# InkTime_v6.net
KiCad netlist of a schematic drawn in EAGLE
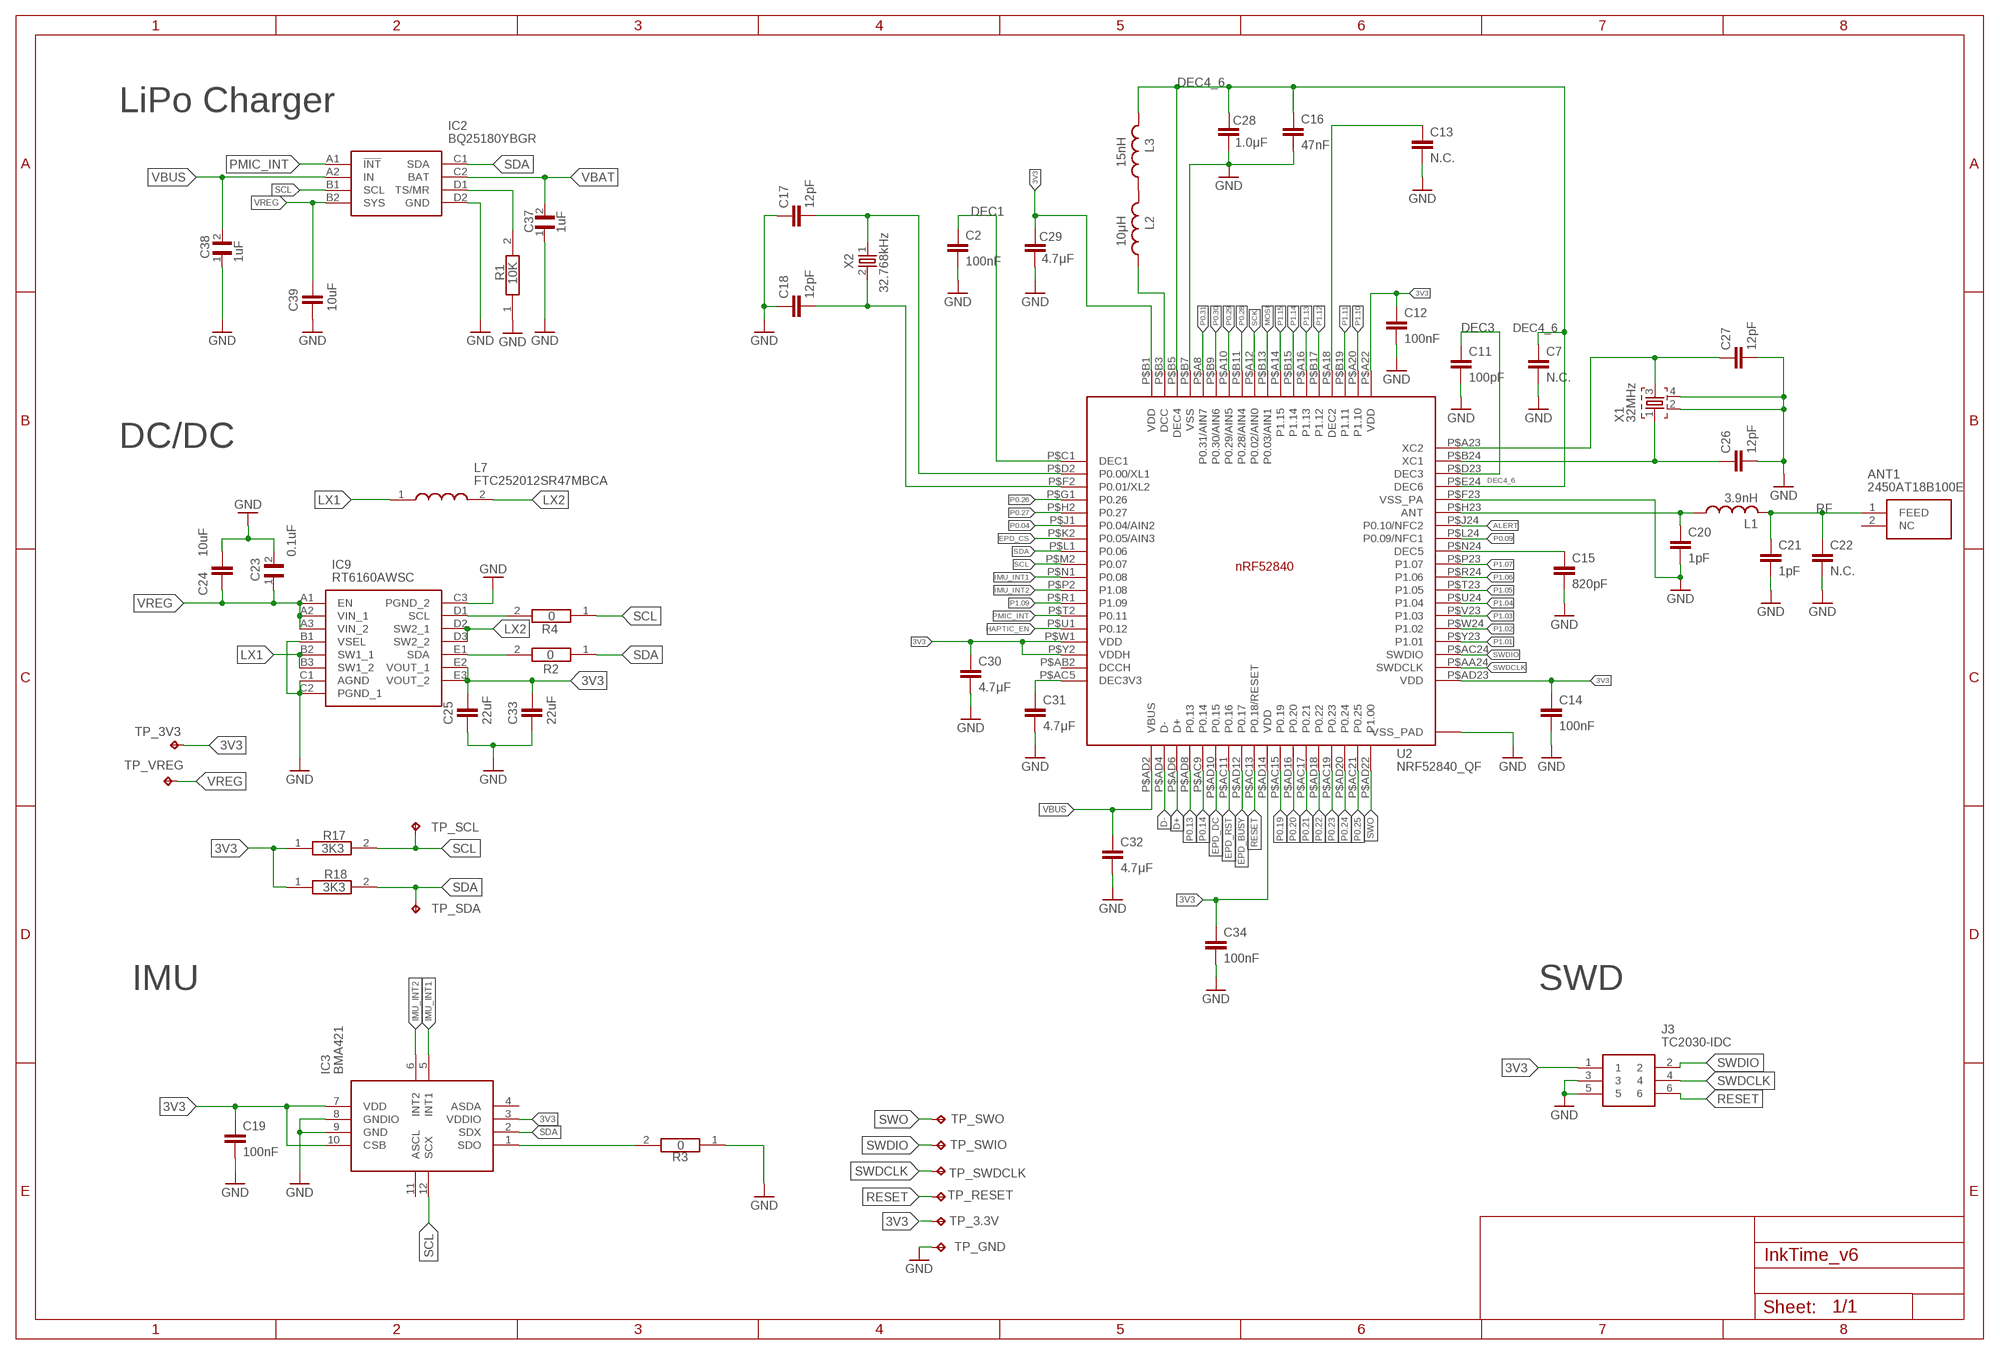
[diagram p0: schematic, sheet 1, part 1 of 2]
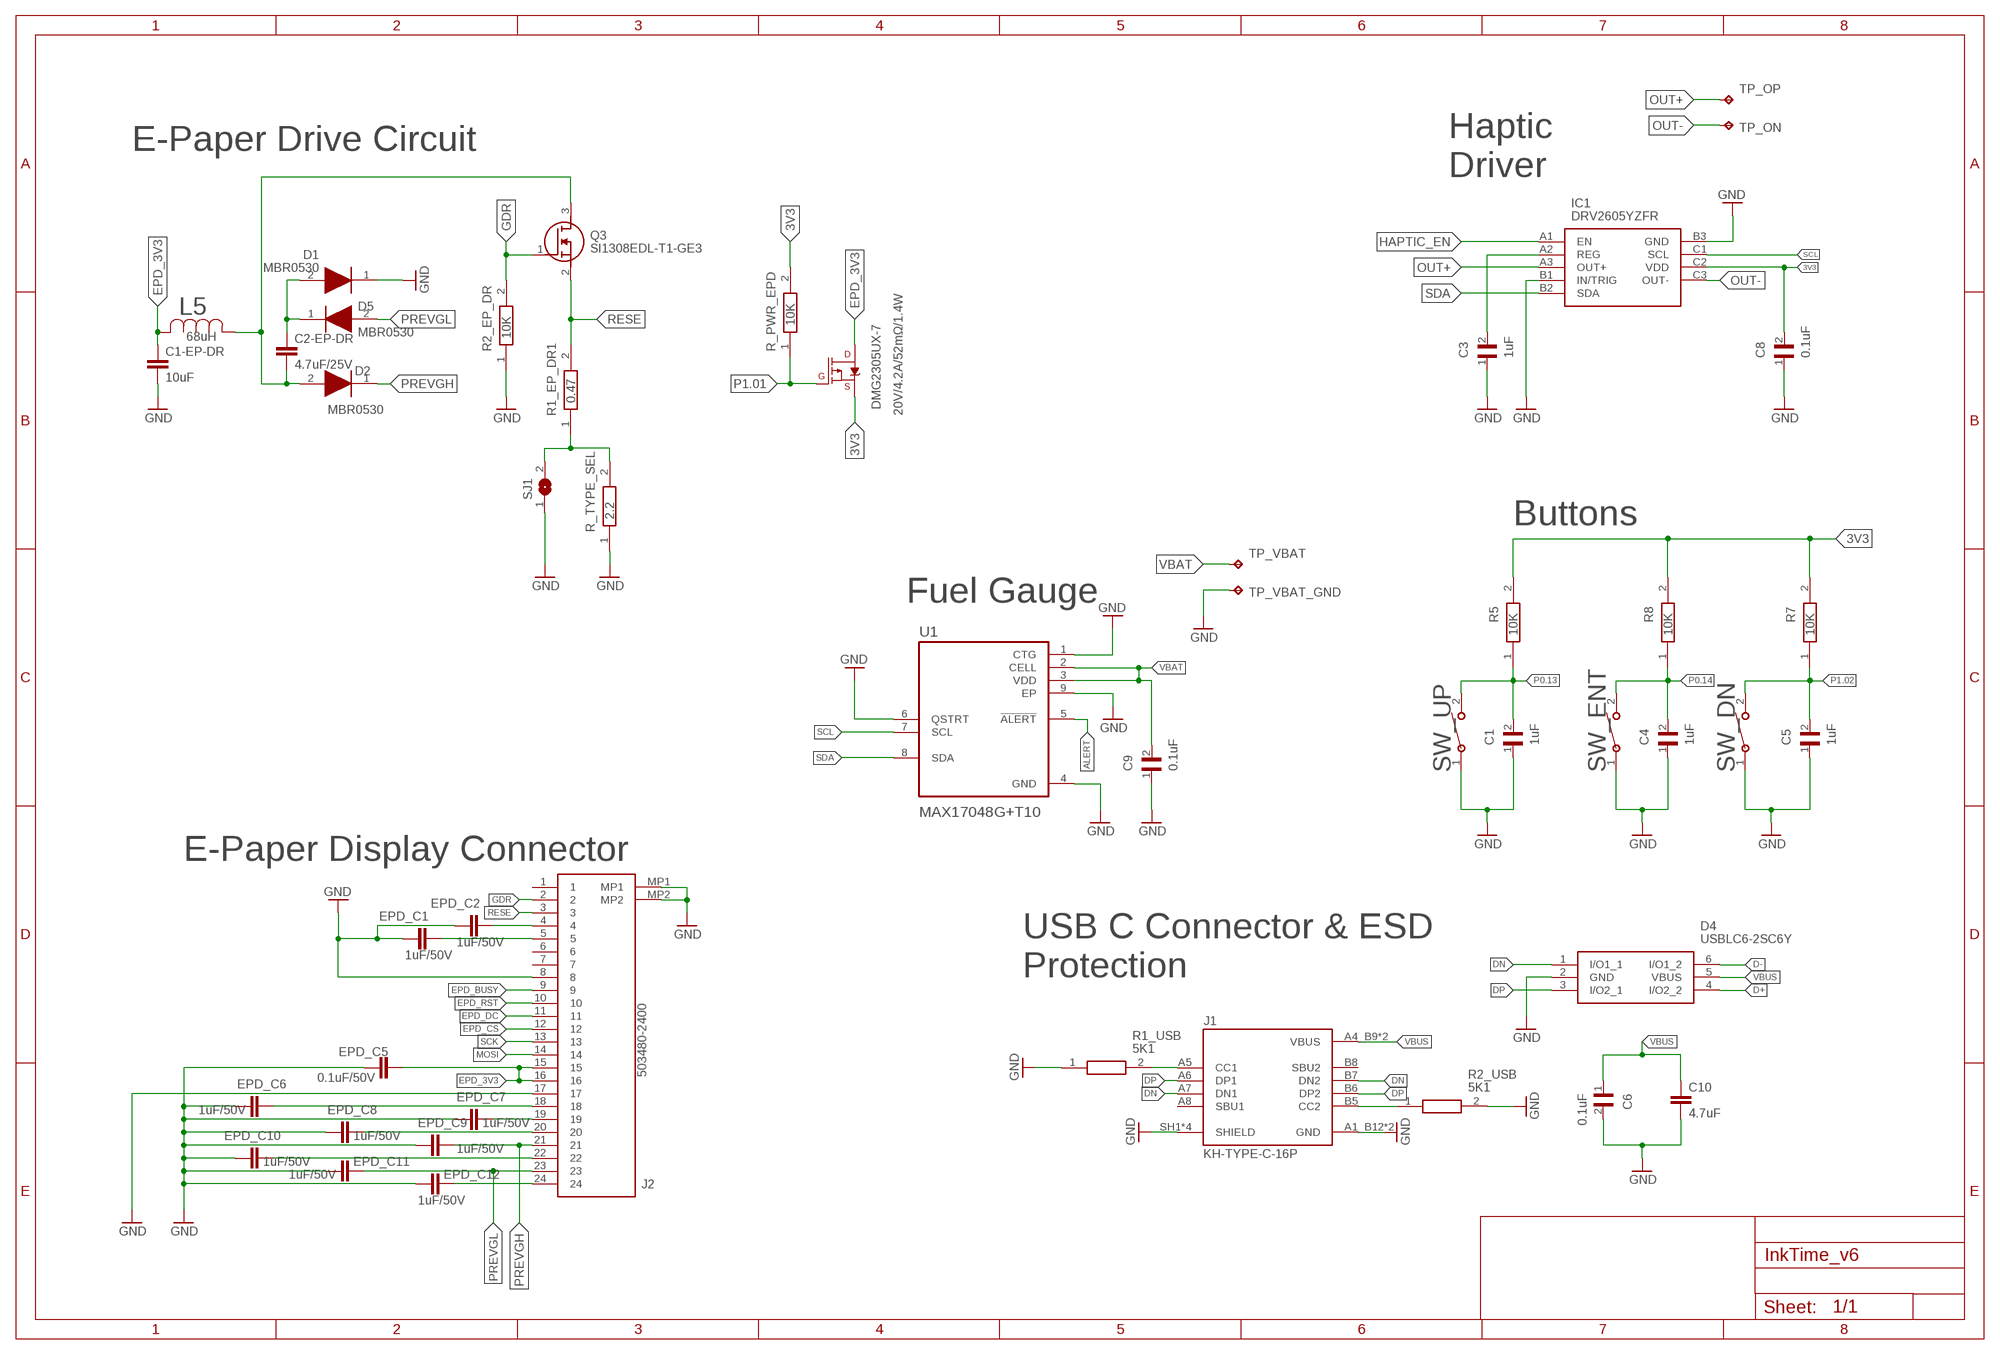
[diagram p1: schematic, sheet 1, part 2 of 2]

(export (version "E")
  (design (tool "Eeschema 10.0.6"))
  (components
    (comp (ref "ANT1")
      (value "2450AT18B100E")
      (footprint "eagle-import:2450AT18B100E_ANTC3216X140N")
      (fields (field (name "MOUSER_PART_NUMBER") "609-2450AT18B100E"))
      (libsource (lib "eagle-import") (part "2450AT18B100E_2450AT18B100E"))
    )
    (comp (ref "C1")
      (value "1uF")
      (footprint "eagle-import:GRM011R60J152KE01L_1_0201")
      (libsource (lib "eagle-import") (part "GRM011R60J152KE01L_1_GRM011R60J152KE01L"))
    )
    (comp (ref "C1-EP-DR")
      (value "10uF")
      (footprint "eagle-import:PERFECT_0402_0402")
      (libsource (lib "eagle-import") (part "PERFECT_0402_CAP_0402"))
    )
    (comp (ref "C2")
      (value "100nF")
      (footprint "eagle-import:NORDIC_NRF_3_RESC0201_L")
      (libsource (lib "eagle-import") (part "NORDIC_NRF_3_CAPACITOR_0201_L"))
    )
    (comp (ref "C2-EP-DR")
      (value "4.7uF/25V")
      (footprint "eagle-import:PERFECT_0402_0402")
      (libsource (lib "eagle-import") (part "PERFECT_0402_CAP_0402"))
    )
    (comp (ref "C3")
      (value "1uF")
      (footprint "eagle-import:GRM011R60J152KE01L_1_0201")
      (libsource (lib "eagle-import") (part "GRM011R60J152KE01L_1_GRM011R60J152KE01L"))
    )
    (comp (ref "C4")
      (value "1uF")
      (footprint "eagle-import:GRM011R60J152KE01L_1_0201")
      (libsource (lib "eagle-import") (part "GRM011R60J152KE01L_1_GRM011R60J152KE01L"))
    )
    (comp (ref "C5")
      (value "1uF")
      (footprint "eagle-import:GRM011R60J152KE01L_1_0201")
      (libsource (lib "eagle-import") (part "GRM011R60J152KE01L_1_GRM011R60J152KE01L"))
    )
    (comp (ref "C6")
      (value "0.1uF")
      (footprint "eagle-import:GRM011R60J152KE01L_1_0201")
      (libsource (lib "eagle-import") (part "GRM011R60J152KE01L_1_GRM011R60J152KE01L"))
    )
    (comp (ref "C7")
      (value "N.C.")
      (footprint "eagle-import:NORDIC_NRF_3_RESC0201_L")
      (libsource (lib "eagle-import") (part "NORDIC_NRF_3_CAPACITOR_0201_L"))
    )
    (comp (ref "C8")
      (value "0.1uF")
      (footprint "eagle-import:GRM011R60J152KE01L_1_0201")
      (libsource (lib "eagle-import") (part "GRM011R60J152KE01L_1_GRM011R60J152KE01L"))
    )
    (comp (ref "C9")
      (value "0.1uF")
      (footprint "eagle-import:GRM011R60J152KE01L_1_0201")
      (libsource (lib "eagle-import") (part "GRM011R60J152KE01L_1_GRM011R60J152KE01L"))
    )
    (comp (ref "C10")
      (value "4.7uF")
      (footprint "eagle-import:PERFECT_0402_0402")
      (libsource (lib "eagle-import") (part "PERFECT_0402_CAP_0402"))
    )
    (comp (ref "C11")
      (value "100pF")
      (footprint "eagle-import:NORDIC_NRF_3_RESC0201_L")
      (libsource (lib "eagle-import") (part "NORDIC_NRF_3_CAPACITOR_0201_L"))
    )
    (comp (ref "C12")
      (value "100nF")
      (footprint "eagle-import:NORDIC_NRF_3_RESC0201_L")
      (libsource (lib "eagle-import") (part "NORDIC_NRF_3_CAPACITOR_0201_L"))
    )
    (comp (ref "C13")
      (value "N.C.")
      (footprint "eagle-import:NORDIC_NRF_3_RESC0201_L")
      (libsource (lib "eagle-import") (part "NORDIC_NRF_3_CAPACITOR_0201_L"))
    )
    (comp (ref "C14")
      (value "100nF")
      (footprint "eagle-import:NORDIC_NRF_3_RESC0201_L")
      (libsource (lib "eagle-import") (part "NORDIC_NRF_3_CAPACITOR_0201_L"))
    )
    (comp (ref "C15")
      (value "820pF")
      (footprint "eagle-import:NORDIC_NRF_3_RESC0201_L")
      (libsource (lib "eagle-import") (part "NORDIC_NRF_3_CAPACITOR_0201_L"))
    )
    (comp (ref "C16")
      (value "47nF")
      (footprint "eagle-import:NORDIC_NRF_3_RESC0201_L")
      (libsource (lib "eagle-import") (part "NORDIC_NRF_3_CAPACITOR_0201_L"))
    )
    (comp (ref "C17")
      (value "12pF")
      (footprint "eagle-import:NORDIC_NRF_3_RESC0201_L")
      (libsource (lib "eagle-import") (part "NORDIC_NRF_3_CAPACITOR_0201_L"))
    )
    (comp (ref "C18")
      (value "12pF")
      (footprint "eagle-import:NORDIC_NRF_3_RESC0201_L")
      (libsource (lib "eagle-import") (part "NORDIC_NRF_3_CAPACITOR_0201_L"))
    )
    (comp (ref "C19")
      (value "100nF")
      (footprint "eagle-import:NORDIC_NRF_3_RESC0201_L")
      (libsource (lib "eagle-import") (part "NORDIC_NRF_3_CAPACITOR_0201_L"))
    )
    (comp (ref "C20")
      (value "1pF")
      (footprint "eagle-import:NORDIC_NRF_3_RESC0201_L")
      (libsource (lib "eagle-import") (part "NORDIC_NRF_3_CAPACITOR_0201_L"))
    )
    (comp (ref "C21")
      (value "1pF")
      (footprint "eagle-import:NORDIC_NRF_3_RESC0201_L")
      (libsource (lib "eagle-import") (part "NORDIC_NRF_3_CAPACITOR_0201_L"))
    )
    (comp (ref "C22")
      (value "N.C.")
      (footprint "eagle-import:NORDIC_NRF_3_RESC0201_L")
      (libsource (lib "eagle-import") (part "NORDIC_NRF_3_CAPACITOR_0201_L"))
    )
    (comp (ref "C23")
      (value "0.1uF")
      (footprint "eagle-import:GRM011R60J152KE01L_2_CAPC0201X13N")
      (fields (field (name "MF") "Murata") (field (name "MP") "GRM011R60J152KE01L"))
      (libsource (lib "eagle-import") (part "GRM011R60J152KE01L_2_GRM011R60J152KE01L"))
    )
    (comp (ref "C24")
      (value "10uF")
      (footprint "eagle-import:NORDIC_NRF_3_RESC0402_L")
      (libsource (lib "eagle-import") (part "NORDIC_NRF_3_CAPACITOR_0402_L"))
    )
    (comp (ref "C25")
      (value "22uF")
      (footprint "eagle-import:NORDIC_NRF_3_RESC0402_L")
      (libsource (lib "eagle-import") (part "NORDIC_NRF_3_CAPACITOR_0402_L"))
    )
    (comp (ref "C26")
      (value "12pF")
      (footprint "eagle-import:NORDIC_NRF_3_RESC0201_L")
      (libsource (lib "eagle-import") (part "NORDIC_NRF_3_CAPACITOR_0201_L"))
    )
    (comp (ref "C27")
      (value "12pF")
      (footprint "eagle-import:NORDIC_NRF_3_RESC0201_L")
      (libsource (lib "eagle-import") (part "NORDIC_NRF_3_CAPACITOR_0201_L"))
    )
    (comp (ref "C28")
      (value "1.0μF")
      (footprint "eagle-import:NORDIC_NRF_3_RESC0402_L")
      (libsource (lib "eagle-import") (part "NORDIC_NRF_3_CAPACITOR_0402_L"))
    )
    (comp (ref "C29")
      (value "4.7μF")
      (footprint "eagle-import:NORDIC_NRF_3_RESC0402_L")
      (libsource (lib "eagle-import") (part "NORDIC_NRF_3_CAPACITOR_0402_L"))
    )
    (comp (ref "C30")
      (value "4.7μF")
      (footprint "eagle-import:NORDIC_NRF_3_RESC0402_L")
      (libsource (lib "eagle-import") (part "NORDIC_NRF_3_CAPACITOR_0402_L"))
    )
    (comp (ref "C31")
      (value "4.7μF")
      (footprint "eagle-import:NORDIC_NRF_3_RESC0402_L")
      (libsource (lib "eagle-import") (part "NORDIC_NRF_3_CAPACITOR_0402_L"))
    )
    (comp (ref "C32")
      (value "4.7μF")
      (footprint "eagle-import:NORDIC_NRF_3_RESC0402_L")
      (libsource (lib "eagle-import") (part "NORDIC_NRF_3_CAPACITOR_0402_L"))
    )
    (comp (ref "C33")
      (value "22uF")
      (footprint "eagle-import:NORDIC_NRF_3_RESC0402_L")
      (libsource (lib "eagle-import") (part "NORDIC_NRF_3_CAPACITOR_0402_L"))
    )
    (comp (ref "C34")
      (value "100nF")
      (footprint "eagle-import:NORDIC_NRF_3_RESC0201_L")
      (libsource (lib "eagle-import") (part "Library_proiect_vf.6mj5mWEzRZml-z0rj9qWig_NORDIC_NRF_3_CAPACITOR_0201_L"))
    )
    (comp (ref "C37")
      (value "1uF")
      (footprint "eagle-import:GRM011R60J152KE01L_2_CAPC0201X13N")
      (fields (field (name "MF") "Murata") (field (name "MP") "GRM011R60J152KE01L"))
      (libsource (lib "eagle-import") (part "GRM011R60J152KE01L_2_GRM011R60J152KE01L"))
    )
    (comp (ref "C38")
      (value "1uF")
      (footprint "eagle-import:GRM011R60J152KE01L_2_CAPC0201X13N")
      (fields (field (name "MF") "Murata") (field (name "MP") "GRM011R60J152KE01L"))
      (libsource (lib "eagle-import") (part "GRM011R60J152KE01L_2_GRM011R60J152KE01L"))
    )
    (comp (ref "C39")
      (value "10uF")
      (footprint "eagle-import:NORDIC_NRF_3_RESC0402_L")
      (libsource (lib "eagle-import") (part "NORDIC_NRF_3_CAPACITOR_0402_L"))
    )
    (comp (ref "D1")
      (value "MBR0530")
      (footprint "eagle-import:ESP32_C6_LIBRARY_5_SOD3716X135N")
      (fields (field (name "MF") "ON Semiconductor"))
      (libsource (lib "eagle-import") (part "ESP32_C6_LIBRARY_5_MBR0530"))
    )
    (comp (ref "D2")
      (value "MBR0530")
      (footprint "eagle-import:ESP32_C6_LIBRARY_5_SOD3716X135N")
      (fields (field (name "MF") "ON Semiconductor"))
      (libsource (lib "eagle-import") (part "ESP32_C6_LIBRARY_5_MBR0530"))
    )
    (comp (ref "D4")
      (value "USBLC6-2SC6Y")
      (footprint "eagle-import:ESP32_C6_LIBRARY_3_SOT95P280X145-6N")
      (fields (field (name "MF") "STMicroelectronics"))
      (libsource (lib "eagle-import") (part "ESP32_C6_LIBRARY_3_USBLC6-2SC6Y"))
    )
    (comp (ref "D5")
      (value "MBR0530")
      (footprint "eagle-import:ESP32_C6_LIBRARY_5_SOD3716X135N")
      (fields (field (name "MF") "ON Semiconductor"))
      (libsource (lib "eagle-import") (part "ESP32_C6_LIBRARY_5_MBR0530"))
    )
    (comp (ref "DMG2305UX-7")
      (value "20V/4.2A/52mΩ/1.4W")
      (footprint "eagle-import:ESP32_C6_LIBRARY_4_ESP32_C6_LIBRARY_4_ESP32_C6_LIBRARY_4_ESP32_C6_LIBRARY_4_ESP32_WROVER_SPARKFUN-DISCRETESEMI_SOT23-3")
      (libsource (lib "eagle-import") (part "ESP32_C6_LIBRARY_4_ESP32_WROVER_SPARKFUN-DISCRETESEMI_MOSFET_PCH-DMG2305UX-7"))
    )
    (comp (ref "EPD_C1")
      (value "1uF/50V")
      (footprint "eagle-import:PERFECT_0402_0402")
      (libsource (lib "eagle-import") (part "PERFECT_0402_CAP_0402"))
    )
    (comp (ref "EPD_C2")
      (value "1uF/50V")
      (footprint "eagle-import:PERFECT_0402_0402")
      (libsource (lib "eagle-import") (part "PERFECT_0402_CAP_0402"))
    )
    (comp (ref "EPD_C5")
      (value "0.1uF/50V")
      (footprint "eagle-import:NORDIC_NRF_3_RESC0201_L")
      (libsource (lib "eagle-import") (part "Library_proiect_vf.6mj5mWEzRZml-z0rj9qWig_NORDIC_NRF_3_CAPACITOR_0201_L"))
    )
    (comp (ref "EPD_C6")
      (value "1uF/50V")
      (footprint "eagle-import:PERFECT_0402_0402")
      (libsource (lib "eagle-import") (part "PERFECT_0402_CAP_0402"))
    )
    (comp (ref "EPD_C7")
      (value "1uF/50V")
      (footprint "eagle-import:PERFECT_0402_0402")
      (libsource (lib "eagle-import") (part "PERFECT_0402_CAP_0402"))
    )
    (comp (ref "EPD_C8")
      (value "1uF/50V")
      (footprint "eagle-import:PERFECT_0402_0402")
      (libsource (lib "eagle-import") (part "PERFECT_0402_CAP_0402"))
    )
    (comp (ref "EPD_C9")
      (value "1uF/50V")
      (footprint "eagle-import:PERFECT_0402_0402")
      (libsource (lib "eagle-import") (part "PERFECT_0402_CAP_0402"))
    )
    (comp (ref "EPD_C10")
      (value "1uF/50V")
      (footprint "eagle-import:PERFECT_0402_0402")
      (libsource (lib "eagle-import") (part "PERFECT_0402_CAP_0402"))
    )
    (comp (ref "EPD_C11")
      (value "1uF/50V")
      (footprint "eagle-import:PERFECT_0402_0402")
      (libsource (lib "eagle-import") (part "PERFECT_0402_CAP_0402"))
    )
    (comp (ref "EPD_C12")
      (value "1uF/50V")
      (footprint "eagle-import:PERFECT_0402_0402")
      (libsource (lib "eagle-import") (part "PERFECT_0402_CAP_0402"))
    )
    (comp (ref "IC1")
      (value "DRV2605YZFR")
      (footprint "eagle-import:DRV2605YZFR_BGA9C50P3X3_144X144X62")
      (libsource (lib "eagle-import") (part "DRV2605YZFR_DRV2605YZFR"))
    )
    (comp (ref "IC2")
      (value "BQ25180YBGR")
      (footprint "eagle-import:BQ25180YBGR_BGA8C40P2X4_100X155X50")
      (fields (field (name "MOUSER_PART_NUMBER") "595-BQ25180YBGR"))
      (libsource (lib "eagle-import") (part "BQ25180YBGR_BQ25180YBGR"))
    )
    (comp (ref "IC3")
      (value "BMA421")
      (footprint "eagle-import:BMA423_BMA423")
      (fields (field (name "ARROW_PART_NUMBER") "BMA423") (field (name "MOUSER_PART_NUMBER") "262-BMA423"))
      (libsource (lib "eagle-import") (part "BMA423_BMA423"))
    )
    (comp (ref "IC9")
      (value "RT6160AWSC")
      (footprint "eagle-import:RT6160AWSC_BGA15C40P3X5_140X230X60")
      (fields (field (name "MOUSER_PART_NUMBER") "835-RT6160AWSC"))
      (libsource (lib "eagle-import") (part "RT6160AWSC_RT6160AWSC"))
    )
    (comp (ref "J1")
      (value "KH-TYPE-C-16P")
      (footprint "eagle-import:KH-TYPE-C-16P_KINGHELM_KH-TYPE-C-16P")
      (fields (field (name "MF") "kinghelm"))
      (libsource (lib "eagle-import") (part "KH-TYPE-C-16P_KH-TYPE-C-16P"))
    )
    (comp (ref "J2")
      (value "503480-2400")
      (footprint "eagle-import:503480-2400_5034802400")
      (fields (field (name "MOUSER_PART_NUMBER") "538-503480-2400"))
      (libsource (lib "eagle-import") (part "503480-2400_503480-2400"))
    )
    (comp (ref "J3")
      (value "TC2030-IDC")
      (footprint "eagle-import:TC2030-IDC_TC2030IDC")
      (libsource (lib "eagle-import") (part "TC2030-IDC_TC2030-IDC"))
    )
    (comp (ref "L1")
      (value "3.9nH")
      (footprint "eagle-import:NORDIC_NRF_2_RESC0402_L")
      (libsource (lib "eagle-import") (part "NORDIC_NRF_2_INDUCTOR_0402_L"))
    )
    (comp (ref "L2")
      (value "10μH")
      (footprint "eagle-import:NORDIC_NRF_2_RESC0402_L")
      (libsource (lib "eagle-import") (part "NORDIC_NRF_2_INDUCTOR_0402_L"))
    )
    (comp (ref "L3")
      (value "15nH")
      (footprint "eagle-import:NORDIC_NRF_2_RESC0402_L")
      (libsource (lib "eagle-import") (part "NORDIC_NRF_2_INDUCTOR_0402_L"))
    )
    (comp (ref "L5")
      (value "68uH")
      (footprint "eagle-import:ESP32_C6_LIBRARY_2_IND_4828-WE-TPC_WRE")
      (fields
        (field (name "MANUFACTURER_PART_NUMBER") "744043680")
        (field (name "COPYRIGHT") "Copyright (C) 2024 Ultra Librarian. All rights reserved.")
      )
      (libsource (lib "eagle-import") (part "ESP32_C6_LIBRARY_2_744043680IND_4828-WE-TPC_WRE"))
    )
    (comp (ref "L7")
      (value "FTC252012SR47MBCA")
      (footprint "eagle-import:MLP2016SR47MT0S1_INDC2016X100N")
      (libsource (lib "eagle-import") (part "MLP2016SR47MT0S1_FTC252012SR47MBCA"))
    )
    (comp (ref "Q3")
      (value "SI1308EDL-T1-GE3")
      (footprint "eagle-import:ESP32_C6_LIBRARY_6_SOT65P210X110-3N")
      (fields (field (name "MF") "Vishay Siliconix"))
      (libsource (lib "eagle-import") (part "ESP32_C6_LIBRARY_6_SI1308EDL-T1-GE3"))
    )
    (comp (ref "R1")
      (value "10K")
      (footprint "eagle-import:CPF0201D7K68C1_0201")
      (libsource (lib "eagle-import") (part "CPF0201D7K68C1_CPF0201D7K68C1"))
    )
    (comp (ref "R1_EP_DR1")
      (value "0.47")
      (footprint "eagle-import:CPF0201D7K68C1_0201")
      (libsource (lib "eagle-import") (part "Library_proiect_vf.6mj5mWEzRZml-z0rj9qWig_CPF0201D7K68C1_CPF0201D7K68C1"))
    )
    (comp (ref "R1_USB")
      (value "5K1")
      (footprint "eagle-import:CPF0201D7K68C1_0201")
      (libsource (lib "eagle-import") (part "Library_proiect_vf.6mj5mWEzRZml-z0rj9qWig_CPF0201D7K68C1_CPF0201D7K68C1"))
    )
    (comp (ref "R2")
      (value "0")
      (footprint "eagle-import:CPF0201D7K68C1_0201")
      (libsource (lib "eagle-import") (part "CPF0201D7K68C1_CPF0201D7K68C1"))
    )
    (comp (ref "R2_EP_DR")
      (value "10K")
      (footprint "eagle-import:CPF0201D7K68C1_0201")
      (libsource (lib "eagle-import") (part "Library_proiect_vf.6mj5mWEzRZml-z0rj9qWig_CPF0201D7K68C1_CPF0201D7K68C1"))
    )
    (comp (ref "R2_USB")
      (value "5K1")
      (footprint "eagle-import:CPF0201D7K68C1_0201")
      (libsource (lib "eagle-import") (part "Library_proiect_vf.6mj5mWEzRZml-z0rj9qWig_CPF0201D7K68C1_CPF0201D7K68C1"))
    )
    (comp (ref "R3")
      (value "0")
      (footprint "eagle-import:CPF0201D7K68C1_0201")
      (libsource (lib "eagle-import") (part "CPF0201D7K68C1_CPF0201D7K68C1"))
    )
    (comp (ref "R4")
      (value "0")
      (footprint "eagle-import:CPF0201D7K68C1_0201")
      (libsource (lib "eagle-import") (part "CPF0201D7K68C1_CPF0201D7K68C1"))
    )
    (comp (ref "R5")
      (value "10K")
      (footprint "eagle-import:CPF0201D7K68C1_0201")
      (libsource (lib "eagle-import") (part "Library_proiect_vf.6mj5mWEzRZml-z0rj9qWig_CPF0201D7K68C1_CPF0201D7K68C1"))
    )
    (comp (ref "R7")
      (value "10K")
      (footprint "eagle-import:CPF0201D7K68C1_0201")
      (libsource (lib "eagle-import") (part "Library_proiect_vf.6mj5mWEzRZml-z0rj9qWig_CPF0201D7K68C1_CPF0201D7K68C1"))
    )
    (comp (ref "R8")
      (value "10K")
      (footprint "eagle-import:CPF0201D7K68C1_0201")
      (libsource (lib "eagle-import") (part "Library_proiect_vf.6mj5mWEzRZml-z0rj9qWig_CPF0201D7K68C1_CPF0201D7K68C1"))
    )
    (comp (ref "R17")
      (value "3K3")
      (footprint "eagle-import:ERA-1AEB3401C_0201")
      (libsource (lib "eagle-import") (part "ERA-1AEB3401C_CPF0201D7K68C1"))
    )
    (comp (ref "R18")
      (value "3K3")
      (footprint "eagle-import:ERA-1AEB3401C_0201")
      (libsource (lib "eagle-import") (part "ERA-1AEB3401C_CPF0201D7K68C1"))
    )
    (comp (ref "R_PWR_EPD")
      (value "10K")
      (footprint "eagle-import:CPF0201D7K68C1_0201")
      (libsource (lib "eagle-import") (part "Library_proiect_vf.6mj5mWEzRZml-z0rj9qWig_CPF0201D7K68C1_CPF0201D7K68C1"))
    )
    (comp (ref "R_TYPE_SEL")
      (value "2.2")
      (footprint "eagle-import:CPF0201D7K68C1_0201")
      (libsource (lib "eagle-import") (part "Library_proiect_vf.6mj5mWEzRZml-z0rj9qWig_CPF0201D7K68C1_CPF0201D7K68C1"))
    )
    (comp (ref "SJ1")
      (value "ESP32_C6_LIBRARY_7_JUMPER_SJ")
      (footprint "eagle-import:ESP32_C6_LIBRARY_7_JUMPER_SJ")
      (libsource (lib "eagle-import") (part "ESP32_C6_LIBRARY_7_JUMPER_SJ"))
    )
    (comp (ref "SW_DN")
      (value "2025-10-22_07-23-44_LIBRARY_EVP-AKE31ASW_EVP-AKE31A_PAN")
      (footprint "eagle-import:2025-10-22_07-23-44_LIBRARY_SW_EVP-AKE31A_PAN")
      (fields
        (field (name "MANUFACTURER_PART_NUMBER") "EVP-AKE31A")
        (field (name "COPYRIGHT") "Copyright (C) 2025 Ultra Librarian. All rights reserved.")
      )
      (libsource (lib "eagle-import") (part "2025-10-22_07-23-44_LIBRARY_EVP-AKE31ASW_EVP-AKE31A_PAN"))
    )
    (comp (ref "SW_ENT")
      (value "2025-10-22_07-23-44_LIBRARY_EVP-AKE31ASW_EVP-AKE31A_PAN")
      (footprint "eagle-import:2025-10-22_07-23-44_LIBRARY_SW_EVP-AKE31A_PAN")
      (fields
        (field (name "MANUFACTURER_PART_NUMBER") "EVP-AKE31A")
        (field (name "COPYRIGHT") "Copyright (C) 2025 Ultra Librarian. All rights reserved.")
      )
      (libsource (lib "eagle-import") (part "2025-10-22_07-23-44_LIBRARY_EVP-AKE31ASW_EVP-AKE31A_PAN"))
    )
    (comp (ref "SW_UP")
      (value "2025-10-22_07-23-44_LIBRARY_EVP-AKE31ASW_EVP-AKE31A_PAN")
      (footprint "eagle-import:2025-10-22_07-23-44_LIBRARY_SW_EVP-AKE31A_PAN")
      (fields
        (field (name "MANUFACTURER_PART_NUMBER") "EVP-AKE31A")
        (field (name "COPYRIGHT") "Copyright (C) 2025 Ultra Librarian. All rights reserved.")
      )
      (libsource (lib "eagle-import") (part "2025-10-22_07-23-44_LIBRARY_EVP-AKE31ASW_EVP-AKE31A_PAN"))
    )
    (comp (ref "TP_3.3V")
      (value "HECTOR_WATCH_1_TPTP20R")
      (footprint "eagle-import:HECTOR_WATCH_1_TP20R")
      (libsource (lib "eagle-import") (part "HECTOR_WATCH_1_TPTP20R"))
    )
    (comp (ref "TP_3V3")
      (value "HECTOR_WATCH_1_TPTP20R")
      (footprint "eagle-import:HECTOR_WATCH_1_TP20R")
      (libsource (lib "eagle-import") (part "HECTOR_WATCH_1_TPTP20R"))
    )
    (comp (ref "TP_GND")
      (value "HECTOR_WATCH_1_TPTP20R")
      (footprint "eagle-import:HECTOR_WATCH_1_TP20R")
      (libsource (lib "eagle-import") (part "HECTOR_WATCH_1_TPTP20R"))
    )
    (comp (ref "TP_ON")
      (value "HECTOR_WATCH_1_TPTP20R")
      (footprint "eagle-import:HECTOR_WATCH_1_TP20R")
      (libsource (lib "eagle-import") (part "Library_proiect_vf.6mj5mWEzRZml-z0rj9qWig_HECTOR_WATCH_1_TPTP20R"))
    )
    (comp (ref "TP_OP")
      (value "HECTOR_WATCH_1_TPTP20R")
      (footprint "eagle-import:HECTOR_WATCH_1_TP20R")
      (libsource (lib "eagle-import") (part "Library_proiect_vf.6mj5mWEzRZml-z0rj9qWig_HECTOR_WATCH_1_TPTP20R"))
    )
    (comp (ref "TP_RESET")
      (value "HECTOR_WATCH_1_TPTP20R")
      (footprint "eagle-import:HECTOR_WATCH_1_TP20R")
      (libsource (lib "eagle-import") (part "HECTOR_WATCH_1_TPTP20R"))
    )
    (comp (ref "TP_SCL")
      (value "HECTOR_WATCH_1_TPTP20R")
      (footprint "eagle-import:HECTOR_WATCH_1_TP20R")
      (libsource (lib "eagle-import") (part "HECTOR_WATCH_1_TPTP20R"))
    )
    (comp (ref "TP_SDA")
      (value "HECTOR_WATCH_1_TPTP20R")
      (footprint "eagle-import:HECTOR_WATCH_1_TP20R")
      (libsource (lib "eagle-import") (part "HECTOR_WATCH_1_TPTP20R"))
    )
    (comp (ref "TP_SWDCLK")
      (value "HECTOR_WATCH_1_TPTP20R")
      (footprint "eagle-import:HECTOR_WATCH_1_TP20R")
      (libsource (lib "eagle-import") (part "HECTOR_WATCH_1_TPTP20R"))
    )
    (comp (ref "TP_SWIO")
      (value "HECTOR_WATCH_1_TPTP20R")
      (footprint "eagle-import:HECTOR_WATCH_1_TP20R")
      (libsource (lib "eagle-import") (part "HECTOR_WATCH_1_TPTP20R"))
    )
    (comp (ref "TP_SWO")
      (value "HECTOR_WATCH_1_TPTP20R")
      (footprint "eagle-import:HECTOR_WATCH_1_TP20R")
      (libsource (lib "eagle-import") (part "HECTOR_WATCH_1_TPTP20R"))
    )
    (comp (ref "TP_VBAT")
      (value "HECTOR_WATCH_1_TPTP20R")
      (footprint "eagle-import:HECTOR_WATCH_1_TP20R")
      (libsource (lib "eagle-import") (part "Library_proiect_vf.6mj5mWEzRZml-z0rj9qWig_HECTOR_WATCH_1_TPTP20R"))
    )
    (comp (ref "TP_VBAT_GND")
      (value "HECTOR_WATCH_1_TPTP20R")
      (footprint "eagle-import:HECTOR_WATCH_1_TP20R")
      (libsource (lib "eagle-import") (part "Library_proiect_vf.6mj5mWEzRZml-z0rj9qWig_HECTOR_WATCH_1_TPTP20R"))
    )
    (comp (ref "TP_VREG")
      (value "HECTOR_WATCH_1_TPTP20R")
      (footprint "eagle-import:HECTOR_WATCH_1_TP20R")
      (libsource (lib "eagle-import") (part "HECTOR_WATCH_1_TPTP20R"))
    )
    (comp (ref "U1")
      (value "MAX17048G+T10")
      (footprint "eagle-import:ESP32_C6_LIBRARY_SON50P200X200X80-9N")
      (fields (field (name "MF") "Analog Devices"))
      (libsource (lib "eagle-import") (part "ESP32_C6_LIBRARY_MAX17048G+T10"))
    )
    (comp (ref "U2")
      (value "NRF52840_QF")
      (footprint "eagle-import:NORDIC_NRF_4_AQFN50P700X700X85_HS-74N")
      (libsource (lib "eagle-import") (part "NORDIC_NRF_4_NRF52840_QF"))
    )
    (comp (ref "X1")
      (value "32MHz")
      (footprint "eagle-import:NORDIC_NRF_BT-XTAL_2016_N")
      (libsource (lib "eagle-import") (part "NORDIC_NRF_XTAL_32MHZ"))
    )
    (comp (ref "X2")
      (value "32.768kHz")
      (footprint "eagle-import:NORDIC_NRF_1_XTAL_3215_N")
      (libsource (lib "eagle-import") (part "NORDIC_NRF_1_XTAL_32KHZ"))
    )
  )
  (nets
    (net (code "1") (name "/DEC1") (class "Default")
      (node (ref "C2") (pin "1") (pinfunction "1_1") (pintype "passive"))
      (node (ref "U2") (pin "P$C1") (pinfunction "DEC1_P$C1") (pintype "power_in"))
    )
    (net (code "2") (name "/DEC3") (class "Default")
      (node (ref "C11") (pin "1") (pinfunction "1_1") (pintype "passive"))
      (node (ref "U2") (pin "P$D23") (pinfunction "DEC3_P$D23") (pintype "bidirectional"))
    )
    (net (code "3") (name "/DEC4_6") (class "Default")
      (node (ref "C16") (pin "1") (pinfunction "1_1") (pintype "passive"))
      (node (ref "C28") (pin "1") (pinfunction "1_1") (pintype "passive"))
      (node (ref "C7") (pin "1") (pinfunction "1_1") (pintype "passive"))
      (node (ref "L3") (pin "2") (pinfunction "2_2") (pintype "passive"))
      (node (ref "U2") (pin "P$B5") (pinfunction "DEC4_P$B5") (pintype "power_in"))
      (node (ref "U2") (pin "P$E24") (pinfunction "DEC6_P$E24") (pintype "bidirectional"))
    )
    (net (code "4") (name "/RF") (class "Default")
      (node (ref "ANT1") (pin "1") (pinfunction "FEED_1") (pintype "input"))
      (node (ref "C21") (pin "1") (pinfunction "1_1") (pintype "passive"))
      (node (ref "C22") (pin "1") (pinfunction "1_1") (pintype "passive"))
      (node (ref "L1") (pin "2") (pinfunction "2_2") (pintype "passive"))
    )
    (net (code "5") (name "3V3") (class "Default")
      (node (ref "C12") (pin "1") (pinfunction "1_1") (pintype "passive"))
      (node (ref "C14") (pin "1") (pinfunction "1_1") (pintype "passive"))
      (node (ref "C19") (pin "1") (pinfunction "1_1") (pintype "passive"))
      (node (ref "C25") (pin "1") (pinfunction "1_1") (pintype "passive"))
      (node (ref "C29") (pin "1") (pinfunction "1_1") (pintype "passive"))
      (node (ref "C30") (pin "1") (pinfunction "1_1") (pintype "passive"))
      (node (ref "C33") (pin "1") (pinfunction "1_1") (pintype "passive"))
      (node (ref "C34") (pin "1") (pinfunction "1_1") (pintype "passive"))
      (node (ref "C8") (pin "2") (pinfunction "2_2") (pintype "passive"))
      (node (ref "DMG2305UX-7") (pin "2") (pinfunction "S_2") (pintype "bidirectional"))
      (node (ref "IC1") (pin "C2") (pinfunction "VDD_C2") (pintype "bidirectional"))
      (node (ref "IC3") (pin "10") (pinfunction "CSB_10") (pintype "bidirectional"))
      (node (ref "IC3") (pin "3") (pinfunction "VDDIO_3") (pintype "bidirectional"))
      (node (ref "IC3") (pin "7") (pinfunction "VDD_7") (pintype "bidirectional"))
      (node (ref "IC9") (pin "E2") (pinfunction "VOUT_1_E2") (pintype "bidirectional"))
      (node (ref "IC9") (pin "E3") (pinfunction "VOUT_2_E3") (pintype "bidirectional"))
      (node (ref "J3") (pin "1") (pinfunction "1_1") (pintype "bidirectional"))
      (node (ref "R17") (pin "1") (pinfunction "1_1") (pintype "bidirectional"))
      (node (ref "R18") (pin "1") (pinfunction "1_1") (pintype "bidirectional"))
      (node (ref "R5") (pin "2") (pinfunction "2_2") (pintype "bidirectional"))
      (node (ref "R7") (pin "2") (pinfunction "2_2") (pintype "bidirectional"))
      (node (ref "R8") (pin "2") (pinfunction "2_2") (pintype "bidirectional"))
      (node (ref "R_PWR_EPD") (pin "2") (pinfunction "2_2") (pintype "bidirectional"))
      (node (ref "TP_3.3V") (pin "TP") (pinfunction "TP_TP") (pintype "input"))
      (node (ref "TP_3V3") (pin "TP") (pinfunction "TP_TP") (pintype "input"))
      (node (ref "U2") (pin "P$A22") (pinfunction "VDD_P$A22") (pintype "power_in"))
      (node (ref "U2") (pin "P$AD14") (pinfunction "VDD_P$AD14") (pintype "power_in"))
      (node (ref "U2") (pin "P$AD23") (pinfunction "VDD_P$AD23") (pintype "power_in"))
      (node (ref "U2") (pin "P$B1") (pinfunction "VDD_P$B1") (pintype "power_in"))
      (node (ref "U2") (pin "P$W1") (pinfunction "VDD_P$W1") (pintype "power_in"))
      (node (ref "U2") (pin "P$Y2") (pinfunction "VDDH_P$Y2") (pintype "power_in"))
    )
    (net (code "6") (name "ALERT") (class "Default")
      (node (ref "U1") (pin "5") (pinfunction "~{ALERT}_5") (pintype "output"))
      (node (ref "U2") (pin "P$J24") (pinfunction "P0.10/NFC2_P$J24") (pintype "bidirectional"))
    )
    (net (code "7") (name "D+") (class "Default")
      (node (ref "D4") (pin "4") (pinfunction "I/O2_2_4") (pintype "bidirectional"))
      (node (ref "U2") (pin "P$AD6") (pinfunction "D+_P$AD6") (pintype "bidirectional"))
    )
    (net (code "8") (name "D-") (class "Default")
      (node (ref "D4") (pin "6") (pinfunction "I/O1_2_6") (pintype "bidirectional"))
      (node (ref "U2") (pin "P$AD4") (pinfunction "D-_P$AD4") (pintype "bidirectional"))
    )
    (net (code "9") (name "DN") (class "Default")
      (node (ref "D4") (pin "1") (pinfunction "I/O1_1_1") (pintype "bidirectional"))
      (node (ref "J1") (pin "A7") (pinfunction "DN1_A7") (pintype "bidirectional"))
      (node (ref "J1") (pin "B7") (pinfunction "DN2_B7") (pintype "bidirectional"))
    )
    (net (code "10") (name "DP") (class "Default")
      (node (ref "D4") (pin "3") (pinfunction "I/O2_1_3") (pintype "bidirectional"))
      (node (ref "J1") (pin "A6") (pinfunction "DP1_A6") (pintype "bidirectional"))
      (node (ref "J1") (pin "B6") (pinfunction "DP2_B6") (pintype "bidirectional"))
    )
    (net (code "11") (name "EPD_3V3") (class "Default")
      (node (ref "C1-EP-DR") (pin "1") (pinfunction "1_1") (pintype "passive"))
      (node (ref "DMG2305UX-7") (pin "3") (pinfunction "D_3") (pintype "bidirectional"))
      (node (ref "EPD_C5") (pin "2") (pinfunction "2_2") (pintype "passive"))
      (node (ref "J2") (pin "15") (pinfunction "15_15") (pintype "bidirectional"))
      (node (ref "J2") (pin "16") (pinfunction "16_16") (pintype "bidirectional"))
      (node (ref "L5") (pin "2") (pinfunction "2_2") (pintype "passive"))
    )
    (net (code "12") (name "EPD_BUSY") (class "Default")
      (node (ref "J2") (pin "9") (pinfunction "9_9") (pintype "bidirectional"))
      (node (ref "U2") (pin "P$AD12") (pinfunction "P0.17_P$AD12") (pintype "bidirectional"))
    )
    (net (code "13") (name "EPD_CS") (class "Default")
      (node (ref "J2") (pin "12") (pinfunction "12_12") (pintype "bidirectional"))
      (node (ref "U2") (pin "P$K2") (pinfunction "P0.05/AIN3_P$K2") (pintype "bidirectional"))
    )
    (net (code "14") (name "EPD_DC") (class "Default")
      (node (ref "J2") (pin "11") (pinfunction "11_11") (pintype "bidirectional"))
      (node (ref "U2") (pin "P$AD10") (pinfunction "P0.15_P$AD10") (pintype "bidirectional"))
    )
    (net (code "15") (name "EPD_RST") (class "Default")
      (node (ref "J2") (pin "10") (pinfunction "10_10") (pintype "bidirectional"))
      (node (ref "U2") (pin "P$AC11") (pinfunction "P0.16_P$AC11") (pintype "bidirectional"))
    )
    (net (code "16") (name "GDR") (class "Default")
      (node (ref "J2") (pin "2") (pinfunction "2_2") (pintype "bidirectional"))
      (node (ref "Q3") (pin "1") (pinfunction "G_1") (pintype "bidirectional"))
      (node (ref "R2_EP_DR") (pin "2") (pinfunction "2_2") (pintype "bidirectional"))
    )
    (net (code "17") (name "GND") (class "Default")
      (node (ref "C1") (pin "1") (pinfunction "1_1") (pintype "passive"))
      (node (ref "C1-EP-DR") (pin "2") (pinfunction "2_2") (pintype "passive"))
      (node (ref "C10") (pin "2") (pinfunction "2_2") (pintype "passive"))
      (node (ref "C11") (pin "2") (pinfunction "2_2") (pintype "passive"))
      (node (ref "C12") (pin "2") (pinfunction "2_2") (pintype "passive"))
      (node (ref "C13") (pin "2") (pinfunction "2_2") (pintype "passive"))
      (node (ref "C14") (pin "2") (pinfunction "2_2") (pintype "passive"))
      (node (ref "C15") (pin "2") (pinfunction "2_2") (pintype "passive"))
      (node (ref "C16") (pin "2") (pinfunction "2_2") (pintype "passive"))
      (node (ref "C17") (pin "1") (pinfunction "1_1") (pintype "passive"))
      (node (ref "C18") (pin "1") (pinfunction "1_1") (pintype "passive"))
      (node (ref "C19") (pin "2") (pinfunction "2_2") (pintype "passive"))
      (node (ref "C2") (pin "2") (pinfunction "2_2") (pintype "passive"))
      (node (ref "C20") (pin "2") (pinfunction "2_2") (pintype "passive"))
      (node (ref "C21") (pin "2") (pinfunction "2_2") (pintype "passive"))
      (node (ref "C22") (pin "2") (pinfunction "2_2") (pintype "passive"))
      (node (ref "C23") (pin "2") (pinfunction "2_2") (pintype "passive"))
      (node (ref "C24") (pin "1") (pinfunction "1_1") (pintype "passive"))
      (node (ref "C25") (pin "2") (pinfunction "2_2") (pintype "passive"))
      (node (ref "C26") (pin "2") (pinfunction "2_2") (pintype "passive"))
      (node (ref "C27") (pin "2") (pinfunction "2_2") (pintype "passive"))
      (node (ref "C28") (pin "2") (pinfunction "2_2") (pintype "passive"))
      (node (ref "C29") (pin "2") (pinfunction "2_2") (pintype "passive"))
      (node (ref "C3") (pin "1") (pinfunction "1_1") (pintype "passive"))
      (node (ref "C30") (pin "2") (pinfunction "2_2") (pintype "passive"))
      (node (ref "C31") (pin "2") (pinfunction "2_2") (pintype "passive"))
      (node (ref "C32") (pin "2") (pinfunction "2_2") (pintype "passive"))
      (node (ref "C33") (pin "2") (pinfunction "2_2") (pintype "passive"))
      (node (ref "C34") (pin "2") (pinfunction "2_2") (pintype "passive"))
      (node (ref "C37") (pin "1") (pinfunction "1_1") (pintype "passive"))
      (node (ref "C38") (pin "1") (pinfunction "1_1") (pintype "passive"))
      (node (ref "C39") (pin "2") (pinfunction "2_2") (pintype "passive"))
      (node (ref "C4") (pin "1") (pinfunction "1_1") (pintype "passive"))
      (node (ref "C5") (pin "1") (pinfunction "1_1") (pintype "passive"))
      (node (ref "C6") (pin "2") (pinfunction "2_2") (pintype "passive"))
      (node (ref "C7") (pin "2") (pinfunction "2_2") (pintype "passive"))
      (node (ref "C8") (pin "1") (pinfunction "1_1") (pintype "passive"))
      (node (ref "C9") (pin "1") (pinfunction "1_1") (pintype "passive"))
      (node (ref "D1") (pin "1") (pinfunction "K_1") (pintype "bidirectional"))
      (node (ref "D4") (pin "2") (pinfunction "GND_2") (pintype "bidirectional"))
      (node (ref "EPD_C1") (pin "2") (pinfunction "2_2") (pintype "passive"))
      (node (ref "EPD_C10") (pin "2") (pinfunction "2_2") (pintype "passive"))
      (node (ref "EPD_C11") (pin "2") (pinfunction "2_2") (pintype "passive"))
      (node (ref "EPD_C12") (pin "2") (pinfunction "2_2") (pintype "passive"))
      (node (ref "EPD_C2") (pin "2") (pinfunction "2_2") (pintype "passive"))
      (node (ref "EPD_C5") (pin "1") (pinfunction "1_1") (pintype "passive"))
      (node (ref "EPD_C6") (pin "2") (pinfunction "2_2") (pintype "passive"))
      (node (ref "EPD_C7") (pin "2") (pinfunction "2_2") (pintype "passive"))
      (node (ref "EPD_C8") (pin "2") (pinfunction "2_2") (pintype "passive"))
      (node (ref "EPD_C9") (pin "2") (pinfunction "2_2") (pintype "passive"))
      (node (ref "IC1") (pin "B1") (pinfunction "IN/TRIG_B1") (pintype "bidirectional"))
      (node (ref "IC1") (pin "B3") (pinfunction "GND_B3") (pintype "bidirectional"))
      (node (ref "IC2") (pin "D2") (pinfunction "GND_D2") (pintype "bidirectional"))
      (node (ref "IC3") (pin "8") (pinfunction "GNDIO_8") (pintype "bidirectional"))
      (node (ref "IC3") (pin "9") (pinfunction "GND_9") (pintype "bidirectional"))
      (node (ref "IC9") (pin "B1") (pinfunction "VSEL_B1") (pintype "bidirectional"))
      (node (ref "IC9") (pin "C1") (pinfunction "AGND_C1") (pintype "bidirectional"))
      (node (ref "IC9") (pin "C2") (pinfunction "PGND_1_C2") (pintype "bidirectional"))
      (node (ref "IC9") (pin "C3") (pinfunction "PGND_2_C3") (pintype "bidirectional"))
      (node (ref "J1") (pin "A12_B1") (pinfunction "GND_A12_B1") (pintype "power_in"))
      (node (ref "J1") (pin "A1_B12") (pinfunction "GND_A1_B12") (pintype "power_in"))
      (node (ref "J1") (pin "SH1") (pinfunction "SHIELD_SH1") (pintype "passive"))
      (node (ref "J1") (pin "SH2") (pinfunction "SHIELD_SH2") (pintype "passive"))
      (node (ref "J1") (pin "SH3") (pinfunction "SHIELD_SH3") (pintype "passive"))
      (node (ref "J1") (pin "SH4") (pinfunction "SHIELD_SH4") (pintype "passive"))
      (node (ref "J2") (pin "17") (pinfunction "17_17") (pintype "bidirectional"))
      (node (ref "J2") (pin "8") (pinfunction "8_8") (pintype "bidirectional"))
      (node (ref "J2") (pin "MP1") (pinfunction "MP1_MP1") (pintype "bidirectional"))
      (node (ref "J2") (pin "MP2") (pinfunction "MP2_MP2") (pintype "bidirectional"))
      (node (ref "J3") (pin "3") (pinfunction "3_3") (pintype "bidirectional"))
      (node (ref "J3") (pin "5") (pinfunction "5_5") (pintype "bidirectional"))
      (node (ref "R1") (pin "1") (pinfunction "1_1") (pintype "bidirectional"))
      (node (ref "R1_USB") (pin "1") (pinfunction "1_1") (pintype "bidirectional"))
      (node (ref "R2_EP_DR") (pin "1") (pinfunction "1_1") (pintype "bidirectional"))
      (node (ref "R2_USB") (pin "2") (pinfunction "2_2") (pintype "bidirectional"))
      (node (ref "R3") (pin "1") (pinfunction "1_1") (pintype "bidirectional"))
      (node (ref "R_TYPE_SEL") (pin "1") (pinfunction "1_1") (pintype "bidirectional"))
      (node (ref "SJ1") (pin "1") (pinfunction "1_1") (pintype "passive"))
      (node (ref "SW_DN") (pin "1") (pinfunction "1_1") (pintype "passive"))
      (node (ref "SW_ENT") (pin "1") (pinfunction "1_1") (pintype "passive"))
      (node (ref "SW_UP") (pin "1") (pinfunction "1_1") (pintype "passive"))
      (node (ref "TP_GND") (pin "TP") (pinfunction "TP_TP") (pintype "input"))
      (node (ref "TP_VBAT_GND") (pin "TP") (pinfunction "TP_TP") (pintype "input"))
      (node (ref "U1") (pin "1") (pinfunction "CTG_1") (pintype "power_in"))
      (node (ref "U1") (pin "4") (pinfunction "GND_4") (pintype "power_in"))
      (node (ref "U1") (pin "6") (pinfunction "QSTRT_6") (pintype "input"))
      (node (ref "U1") (pin "9") (pinfunction "EP_9") (pintype "power_in"))
      (node (ref "U2") (pin "P$74") (pinfunction "VSS_PAD_P$74") (pintype "bidirectional"))
      (node (ref "U2") (pin "P$75") (pinfunction "VSS_PAD_P$75") (pintype "bidirectional"))
      (node (ref "U2") (pin "P$76") (pinfunction "VSS_PAD_P$76") (pintype "bidirectional"))
      (node (ref "U2") (pin "P$77") (pinfunction "VSS_PAD_P$77") (pintype "bidirectional"))
      (node (ref "U2") (pin "P$78") (pinfunction "VSS_PAD_P$78") (pintype "bidirectional"))
      (node (ref "U2") (pin "P$79") (pinfunction "VSS_PAD_P$79") (pintype "bidirectional"))
      (node (ref "U2") (pin "P$80") (pinfunction "VSS_PAD_P$80") (pintype "bidirectional"))
      (node (ref "U2") (pin "P$81") (pinfunction "VSS_PAD_P$81") (pintype "bidirectional"))
      (node (ref "U2") (pin "P$82") (pinfunction "VSS_PAD_P$82") (pintype "bidirectional"))
      (node (ref "U2") (pin "P$83") (pinfunction "VSS_PAD_P$83") (pintype "bidirectional"))
      (node (ref "U2") (pin "P$84") (pinfunction "VSS_PAD_P$84") (pintype "bidirectional"))
      (node (ref "U2") (pin "P$85") (pinfunction "VSS_PAD_P$85") (pintype "bidirectional"))
      (node (ref "U2") (pin "P$86") (pinfunction "VSS_PAD_P$86") (pintype "bidirectional"))
      (node (ref "U2") (pin "P$87") (pinfunction "VSS_PAD_P$87") (pintype "bidirectional"))
      (node (ref "U2") (pin "P$88") (pinfunction "VSS_PAD_P$88") (pintype "bidirectional"))
      (node (ref "U2") (pin "P$89") (pinfunction "VSS_PAD_P$89") (pintype "bidirectional"))
      (node (ref "U2") (pin "P$90") (pinfunction "VSS_PAD_P$90") (pintype "bidirectional"))
      (node (ref "U2") (pin "P$B7") (pinfunction "VSS_P$B7") (pintype "power_in"))
      (node (ref "U2") (pin "P$F23") (pinfunction "VSS_PA_P$F23") (pintype "bidirectional"))
      (node (ref "X1") (pin "2") (pinfunction "2_2") (pintype "passive"))
      (node (ref "X1") (pin "4") (pinfunction "4_4") (pintype "passive"))
    )
    (net (code "18") (name "HAPTIC_EN") (class "Default")
      (node (ref "IC1") (pin "A1") (pinfunction "EN_A1") (pintype "bidirectional"))
      (node (ref "U2") (pin "P$U1") (pinfunction "P0.12_P$U1") (pintype "bidirectional"))
    )
    (net (code "19") (name "IMU_INT1") (class "Default")
      (node (ref "IC3") (pin "5") (pinfunction "INT1_5") (pintype "bidirectional"))
      (node (ref "U2") (pin "P$N1") (pinfunction "P0.08_P$N1") (pintype "bidirectional"))
    )
    (net (code "20") (name "IMU_INT2") (class "Default")
      (node (ref "IC3") (pin "6") (pinfunction "INT2_6") (pintype "bidirectional"))
      (node (ref "U2") (pin "P$P2") (pinfunction "P1.08_P$P2") (pintype "bidirectional"))
    )
    (net (code "21") (name "LX1") (class "Default")
      (node (ref "IC9") (pin "B2") (pinfunction "SW1_1_B2") (pintype "bidirectional"))
      (node (ref "IC9") (pin "B3") (pinfunction "SW1_2_B3") (pintype "bidirectional"))
      (node (ref "L7") (pin "1") (pinfunction "1_1") (pintype "bidirectional"))
    )
    (net (code "22") (name "LX2") (class "Default")
      (node (ref "IC9") (pin "D2") (pinfunction "SW2_1_D2") (pintype "bidirectional"))
      (node (ref "IC9") (pin "D3") (pinfunction "SW2_2_D3") (pintype "bidirectional"))
      (node (ref "L7") (pin "2") (pinfunction "2_2") (pintype "bidirectional"))
    )
    (net (code "23") (name "MOSI") (class "Default")
      (node (ref "J2") (pin "14") (pinfunction "14_14") (pintype "bidirectional"))
      (node (ref "U2") (pin "P$B13") (pinfunction "P0.03/AIN1_P$B13") (pintype "bidirectional"))
    )
    (net (code "24") (name "Net-(D1-A)") (class "Default")
      (node (ref "C2-EP-DR") (pin "1") (pinfunction "1_1") (pintype "passive"))
      (node (ref "D1") (pin "2") (pinfunction "A_2") (pintype "bidirectional"))
      (node (ref "D5") (pin "1") (pinfunction "K_1") (pintype "bidirectional"))
    )
    (net (code "25") (name "Net-(D2-A)") (class "Default")
      (node (ref "C2-EP-DR") (pin "2") (pinfunction "2_2") (pintype "passive"))
      (node (ref "D2") (pin "2") (pinfunction "A_2") (pintype "bidirectional"))
      (node (ref "L5") (pin "1") (pinfunction "1_1") (pintype "passive"))
      (node (ref "Q3") (pin "3") (pinfunction "D_3") (pintype "bidirectional"))
    )
    (net (code "26") (name "Net-(EPD_C1-Pad1)") (class "Default")
      (node (ref "EPD_C1") (pin "1") (pinfunction "1_1") (pintype "passive"))
      (node (ref "J2") (pin "5") (pinfunction "5_5") (pintype "bidirectional"))
    )
    (net (code "27") (name "Net-(EPD_C2-Pad1)") (class "Default")
      (node (ref "EPD_C2") (pin "1") (pinfunction "1_1") (pintype "passive"))
      (node (ref "J2") (pin "4") (pinfunction "4_4") (pintype "bidirectional"))
    )
    (net (code "28") (name "Net-(EPD_C6-Pad1)") (class "Default")
      (node (ref "EPD_C6") (pin "1") (pinfunction "1_1") (pintype "passive"))
      (node (ref "J2") (pin "18") (pinfunction "18_18") (pintype "bidirectional"))
    )
    (net (code "29") (name "Net-(EPD_C7-Pad1)") (class "Default")
      (node (ref "EPD_C7") (pin "1") (pinfunction "1_1") (pintype "passive"))
      (node (ref "J2") (pin "19") (pinfunction "19_19") (pintype "bidirectional"))
    )
    (net (code "30") (name "Net-(EPD_C8-Pad1)") (class "Default")
      (node (ref "EPD_C8") (pin "1") (pinfunction "1_1") (pintype "passive"))
      (node (ref "J2") (pin "20") (pinfunction "20_20") (pintype "bidirectional"))
    )
    (net (code "31") (name "Net-(EPD_C10-Pad1)") (class "Default")
      (node (ref "EPD_C10") (pin "1") (pinfunction "1_1") (pintype "passive"))
      (node (ref "J2") (pin "22") (pinfunction "22_22") (pintype "bidirectional"))
    )
    (net (code "32") (name "Net-(EPD_C12-Pad1)") (class "Default")
      (node (ref "EPD_C12") (pin "1") (pinfunction "1_1") (pintype "passive"))
      (node (ref "J2") (pin "24") (pinfunction "24_24") (pintype "bidirectional"))
    )
    (net (code "33") (name "Net-(IC1-REG)") (class "Default")
      (node (ref "C3") (pin "2") (pinfunction "2_2") (pintype "passive"))
      (node (ref "IC1") (pin "A2") (pinfunction "REG_A2") (pintype "bidirectional"))
    )
    (net (code "34") (name "Net-(IC2-TS{slash}MR)") (class "Default")
      (node (ref "IC2") (pin "D1") (pinfunction "TS/MR_D1") (pintype "bidirectional"))
      (node (ref "R1") (pin "2") (pinfunction "2_2") (pintype "bidirectional"))
    )
    (net (code "35") (name "Net-(IC3-SDO)") (class "Default")
      (node (ref "IC3") (pin "1") (pinfunction "SDO_1") (pintype "bidirectional"))
      (node (ref "R3") (pin "2") (pinfunction "2_2") (pintype "bidirectional"))
    )
    (net (code "36") (name "Net-(IC9-SCL)") (class "Default")
      (node (ref "IC9") (pin "D1") (pinfunction "SCL_D1") (pintype "bidirectional"))
      (node (ref "R4") (pin "2") (pinfunction "2_2") (pintype "bidirectional"))
    )
    (net (code "37") (name "Net-(IC9-SDA)") (class "Default")
      (node (ref "IC9") (pin "E1") (pinfunction "SDA_E1") (pintype "bidirectional"))
      (node (ref "R2") (pin "2") (pinfunction "2_2") (pintype "bidirectional"))
    )
    (net (code "38") (name "Net-(J1-CC1)") (class "Default")
      (node (ref "J1") (pin "A5") (pinfunction "CC1_A5") (pintype "bidirectional"))
      (node (ref "R1_USB") (pin "2") (pinfunction "2_2") (pintype "bidirectional"))
    )
    (net (code "39") (name "Net-(J1-CC2)") (class "Default")
      (node (ref "J1") (pin "B5") (pinfunction "CC2_B5") (pintype "bidirectional"))
      (node (ref "R2_USB") (pin "1") (pinfunction "1_1") (pintype "bidirectional"))
    )
    (net (code "40") (name "Net-(L2-Pad2)") (class "Default")
      (node (ref "L2") (pin "2") (pinfunction "2_2") (pintype "passive"))
      (node (ref "L3") (pin "1") (pinfunction "1_1") (pintype "passive"))
    )
    (net (code "41") (name "Net-(R1_EP_DR1-Pad1)") (class "Default")
      (node (ref "R1_EP_DR1") (pin "1") (pinfunction "1_1") (pintype "bidirectional"))
      (node (ref "R_TYPE_SEL") (pin "2") (pinfunction "2_2") (pintype "bidirectional"))
      (node (ref "SJ1") (pin "2") (pinfunction "2_2") (pintype "passive"))
    )
    (net (code "42") (name "Net-(U2-ANT)") (class "Default")
      (node (ref "C20") (pin "1") (pinfunction "1_1") (pintype "passive"))
      (node (ref "L1") (pin "1") (pinfunction "1_1") (pintype "passive"))
      (node (ref "U2") (pin "P$H23") (pinfunction "ANT_P$H23") (pintype "bidirectional"))
    )
    (net (code "43") (name "Net-(U2-DCC)") (class "Default")
      (node (ref "L2") (pin "1") (pinfunction "1_1") (pintype "passive"))
      (node (ref "U2") (pin "P$B3") (pinfunction "DCC_P$B3") (pintype "output"))
    )
    (net (code "44") (name "Net-(U2-DEC2)") (class "Default")
      (node (ref "C13") (pin "1") (pinfunction "1_1") (pintype "passive"))
      (node (ref "U2") (pin "P$A18") (pinfunction "DEC2_P$A18") (pintype "bidirectional"))
    )
    (net (code "45") (name "Net-(U2-DEC3V3)") (class "Default")
      (node (ref "C31") (pin "1") (pinfunction "1_1") (pintype "passive"))
      (node (ref "U2") (pin "P$AC5") (pinfunction "DEC3V3_P$AC5") (pintype "bidirectional"))
    )
    (net (code "46") (name "Net-(U2-DEC5)") (class "Default")
      (node (ref "C15") (pin "1") (pinfunction "1_1") (pintype "passive"))
      (node (ref "U2") (pin "P$N24") (pinfunction "DEC5_P$N24") (pintype "bidirectional"))
    )
    (net (code "47") (name "Net-(U2-P0.00{slash}XL1)") (class "Default")
      (node (ref "C17") (pin "2") (pinfunction "2_2") (pintype "passive"))
      (node (ref "U2") (pin "P$D2") (pinfunction "P0.00/XL1_P$D2") (pintype "bidirectional"))
      (node (ref "X2") (pin "1") (pinfunction "1_1") (pintype "passive"))
    )
    (net (code "48") (name "Net-(U2-P0.01{slash}XL2)") (class "Default")
      (node (ref "C18") (pin "2") (pinfunction "2_2") (pintype "passive"))
      (node (ref "U2") (pin "P$F2") (pinfunction "P0.01/XL2_P$F2") (pintype "bidirectional"))
      (node (ref "X2") (pin "2") (pinfunction "2_2") (pintype "passive"))
    )
    (net (code "49") (name "Net-(U2-XC1)") (class "Default")
      (node (ref "C26") (pin "1") (pinfunction "1_1") (pintype "passive"))
      (node (ref "U2") (pin "P$B24") (pinfunction "XC1_P$B24") (pintype "input"))
      (node (ref "X1") (pin "1") (pinfunction "1_1") (pintype "passive"))
    )
    (net (code "50") (name "Net-(U2-XC2)") (class "Default")
      (node (ref "C27") (pin "1") (pinfunction "1_1") (pintype "passive"))
      (node (ref "U2") (pin "P$A23") (pinfunction "XC2_P$A23") (pintype "output"))
      (node (ref "X1") (pin "3") (pinfunction "3_3") (pintype "passive"))
    )
    (net (code "51") (name "OUT+") (class "Default")
      (node (ref "IC1") (pin "A3") (pinfunction "OUT+_A3") (pintype "bidirectional"))
      (node (ref "TP_OP") (pin "TP") (pinfunction "TP_TP") (pintype "input"))
    )
    (net (code "52") (name "OUT-") (class "Default")
      (node (ref "IC1") (pin "C3") (pinfunction "OUT-_C3") (pintype "bidirectional"))
      (node (ref "TP_ON") (pin "TP") (pinfunction "TP_TP") (pintype "input"))
    )
    (net (code "53") (name "P0.04") (class "Default")
      (node (ref "U2") (pin "P$J1") (pinfunction "P0.04/AIN2_P$J1") (pintype "bidirectional"))
    )
    (net (code "54") (name "P0.09") (class "Default")
      (node (ref "U2") (pin "P$L24") (pinfunction "P0.09/NFC1_P$L24") (pintype "bidirectional"))
    )
    (net (code "55") (name "P0.13") (class "Default")
      (node (ref "C1") (pin "2") (pinfunction "2_2") (pintype "passive"))
      (node (ref "R5") (pin "1") (pinfunction "1_1") (pintype "bidirectional"))
      (node (ref "SW_UP") (pin "2") (pinfunction "2_2") (pintype "passive"))
      (node (ref "U2") (pin "P$AD8") (pinfunction "P0.13_P$AD8") (pintype "bidirectional"))
    )
    (net (code "56") (name "P0.14") (class "Default")
      (node (ref "C4") (pin "2") (pinfunction "2_2") (pintype "passive"))
      (node (ref "R8") (pin "1") (pinfunction "1_1") (pintype "bidirectional"))
      (node (ref "SW_ENT") (pin "2") (pinfunction "2_2") (pintype "passive"))
      (node (ref "U2") (pin "P$AC9") (pinfunction "P0.14_P$AC9") (pintype "bidirectional"))
    )
    (net (code "57") (name "P0.19") (class "Default")
      (node (ref "U2") (pin "P$AC15") (pinfunction "P0.19_P$AC15") (pintype "bidirectional"))
    )
    (net (code "58") (name "P0.20") (class "Default")
      (node (ref "U2") (pin "P$AD16") (pinfunction "P0.20_P$AD16") (pintype "bidirectional"))
    )
    (net (code "59") (name "P0.21") (class "Default")
      (node (ref "U2") (pin "P$AC17") (pinfunction "P0.21_P$AC17") (pintype "bidirectional"))
    )
    (net (code "60") (name "P0.22") (class "Default")
      (node (ref "U2") (pin "P$AD18") (pinfunction "P0.22_P$AD18") (pintype "bidirectional"))
    )
    (net (code "61") (name "P0.23") (class "Default")
      (node (ref "U2") (pin "P$AC19") (pinfunction "P0.23_P$AC19") (pintype "bidirectional"))
    )
    (net (code "62") (name "P0.24") (class "Default")
      (node (ref "U2") (pin "P$AD20") (pinfunction "P0.24_P$AD20") (pintype "bidirectional"))
    )
    (net (code "63") (name "P0.25") (class "Default")
      (node (ref "U2") (pin "P$AC21") (pinfunction "P0.25_P$AC21") (pintype "bidirectional"))
    )
    (net (code "64") (name "P0.26") (class "Default")
      (node (ref "U2") (pin "P$G1") (pinfunction "P0.26_P$G1") (pintype "bidirectional"))
    )
    (net (code "65") (name "P0.27") (class "Default")
      (node (ref "U2") (pin "P$H2") (pinfunction "P0.27_P$H2") (pintype "bidirectional"))
    )
    (net (code "66") (name "P0.28") (class "Default")
      (node (ref "U2") (pin "P$B11") (pinfunction "P0.28/AIN4_P$B11") (pintype "bidirectional"))
    )
    (net (code "67") (name "P0.29") (class "Default")
      (node (ref "U2") (pin "P$A10") (pinfunction "P0.29/AIN5_P$A10") (pintype "bidirectional"))
    )
    (net (code "68") (name "P0.30") (class "Default")
      (node (ref "U2") (pin "P$B9") (pinfunction "P0.30/AIN6_P$B9") (pintype "bidirectional"))
    )
    (net (code "69") (name "P0.31") (class "Default")
      (node (ref "U2") (pin "P$A8") (pinfunction "P0.31/AIN7_P$A8") (pintype "bidirectional"))
    )
    (net (code "70") (name "P1.01") (class "Default")
      (node (ref "DMG2305UX-7") (pin "1") (pinfunction "G_1") (pintype "bidirectional"))
      (node (ref "R_PWR_EPD") (pin "1") (pinfunction "1_1") (pintype "bidirectional"))
      (node (ref "U2") (pin "P$Y23") (pinfunction "P1.01_P$Y23") (pintype "bidirectional"))
    )
    (net (code "71") (name "P1.02") (class "Default")
      (node (ref "C5") (pin "2") (pinfunction "2_2") (pintype "passive"))
      (node (ref "R7") (pin "1") (pinfunction "1_1") (pintype "bidirectional"))
      (node (ref "SW_DN") (pin "2") (pinfunction "2_2") (pintype "passive"))
      (node (ref "U2") (pin "P$W24") (pinfunction "P1.02_P$W24") (pintype "bidirectional"))
    )
    (net (code "72") (name "P1.03") (class "Default")
      (node (ref "U2") (pin "P$V23") (pinfunction "P1.03_P$V23") (pintype "bidirectional"))
    )
    (net (code "73") (name "P1.04") (class "Default")
      (node (ref "U2") (pin "P$U24") (pinfunction "P1.04_P$U24") (pintype "bidirectional"))
    )
    (net (code "74") (name "P1.05") (class "Default")
      (node (ref "U2") (pin "P$T23") (pinfunction "P1.05_P$T23") (pintype "bidirectional"))
    )
    (net (code "75") (name "P1.06") (class "Default")
      (node (ref "U2") (pin "P$R24") (pinfunction "P1.06_P$R24") (pintype "bidirectional"))
    )
    (net (code "76") (name "P1.07") (class "Default")
      (node (ref "U2") (pin "P$P23") (pinfunction "P1.07_P$P23") (pintype "bidirectional"))
    )
    (net (code "77") (name "P1.09") (class "Default")
      (node (ref "U2") (pin "P$R1") (pinfunction "P1.09_P$R1") (pintype "bidirectional"))
    )
    (net (code "78") (name "P1.10") (class "Default")
      (node (ref "U2") (pin "P$A20") (pinfunction "P1.10_P$A20") (pintype "bidirectional"))
    )
    (net (code "79") (name "P1.11") (class "Default")
      (node (ref "U2") (pin "P$B19") (pinfunction "P1.11_P$B19") (pintype "bidirectional"))
    )
    (net (code "80") (name "P1.12") (class "Default")
      (node (ref "U2") (pin "P$B17") (pinfunction "P1.12_P$B17") (pintype "bidirectional"))
    )
    (net (code "81") (name "P1.13") (class "Default")
      (node (ref "U2") (pin "P$A16") (pinfunction "P1.13_P$A16") (pintype "bidirectional"))
    )
    (net (code "82") (name "P1.14") (class "Default")
      (node (ref "U2") (pin "P$B15") (pinfunction "P1.14_P$B15") (pintype "bidirectional"))
    )
    (net (code "83") (name "P1.15") (class "Default")
      (node (ref "U2") (pin "P$A14") (pinfunction "P1.15_P$A14") (pintype "bidirectional"))
    )
    (net (code "84") (name "PMIC_INT") (class "Default")
      (node (ref "IC2") (pin "A1") (pinfunction "~{INT}_A1") (pintype "bidirectional"))
      (node (ref "U2") (pin "P$T2") (pinfunction "P0.11_P$T2") (pintype "bidirectional"))
    )
    (net (code "85") (name "PREVGH") (class "Default")
      (node (ref "D2") (pin "1") (pinfunction "K_1") (pintype "bidirectional"))
      (node (ref "EPD_C9") (pin "1") (pinfunction "1_1") (pintype "passive"))
      (node (ref "J2") (pin "21") (pinfunction "21_21") (pintype "bidirectional"))
    )
    (net (code "86") (name "PREVGL") (class "Default")
      (node (ref "D5") (pin "2") (pinfunction "A_2") (pintype "bidirectional"))
      (node (ref "EPD_C11") (pin "1") (pinfunction "1_1") (pintype "passive"))
      (node (ref "J2") (pin "23") (pinfunction "23_23") (pintype "bidirectional"))
    )
    (net (code "87") (name "RESE") (class "Default")
      (node (ref "J2") (pin "3") (pinfunction "3_3") (pintype "bidirectional"))
      (node (ref "Q3") (pin "2") (pinfunction "S_2") (pintype "bidirectional"))
      (node (ref "R1_EP_DR1") (pin "2") (pinfunction "2_2") (pintype "bidirectional"))
    )
    (net (code "88") (name "RESET") (class "Default")
      (node (ref "J3") (pin "6") (pinfunction "6_6") (pintype "bidirectional"))
      (node (ref "TP_RESET") (pin "TP") (pinfunction "TP_TP") (pintype "input"))
      (node (ref "U2") (pin "P$AC13") (pinfunction "P0.18/RESET_P$AC13") (pintype "bidirectional"))
    )
    (net (code "89") (name "SCK") (class "Default")
      (node (ref "J2") (pin "13") (pinfunction "13_13") (pintype "bidirectional"))
      (node (ref "U2") (pin "P$A12") (pinfunction "P0.02/AIN0_P$A12") (pintype "bidirectional"))
    )
    (net (code "90") (name "SCL") (class "Default")
      (node (ref "IC1") (pin "C1") (pinfunction "SCL_C1") (pintype "bidirectional"))
      (node (ref "IC2") (pin "B1") (pinfunction "SCL_B1") (pintype "bidirectional"))
      (node (ref "IC3") (pin "12") (pinfunction "SCX_12") (pintype "bidirectional"))
      (node (ref "R17") (pin "2") (pinfunction "2_2") (pintype "bidirectional"))
      (node (ref "R4") (pin "1") (pinfunction "1_1") (pintype "bidirectional"))
      (node (ref "TP_SCL") (pin "TP") (pinfunction "TP_TP") (pintype "input"))
      (node (ref "U1") (pin "7") (pinfunction "SCL_7") (pintype "input"))
      (node (ref "U2") (pin "P$M2") (pinfunction "P0.07_P$M2") (pintype "bidirectional"))
    )
    (net (code "91") (name "SDA") (class "Default")
      (node (ref "IC1") (pin "B2") (pinfunction "SDA_B2") (pintype "bidirectional"))
      (node (ref "IC2") (pin "C1") (pinfunction "SDA_C1") (pintype "bidirectional"))
      (node (ref "IC3") (pin "2") (pinfunction "SDX_2") (pintype "bidirectional"))
      (node (ref "R18") (pin "2") (pinfunction "2_2") (pintype "bidirectional"))
      (node (ref "R2") (pin "1") (pinfunction "1_1") (pintype "bidirectional"))
      (node (ref "TP_SDA") (pin "TP") (pinfunction "TP_TP") (pintype "input"))
      (node (ref "U1") (pin "8") (pinfunction "SDA_8") (pintype "bidirectional"))
      (node (ref "U2") (pin "P$L1") (pinfunction "P0.06_P$L1") (pintype "bidirectional"))
    )
    (net (code "92") (name "SWDCLK") (class "Default")
      (node (ref "J3") (pin "4") (pinfunction "4_4") (pintype "bidirectional"))
      (node (ref "TP_SWDCLK") (pin "TP") (pinfunction "TP_TP") (pintype "input"))
      (node (ref "U2") (pin "P$AA24") (pinfunction "SWDCLK_P$AA24") (pintype "input"))
    )
    (net (code "93") (name "SWDIO") (class "Default")
      (node (ref "J3") (pin "2") (pinfunction "2_2") (pintype "bidirectional"))
      (node (ref "TP_SWIO") (pin "TP") (pinfunction "TP_TP") (pintype "input"))
      (node (ref "U2") (pin "P$AC24") (pinfunction "SWDIO_P$AC24") (pintype "bidirectional"))
    )
    (net (code "94") (name "SWO") (class "Default")
      (node (ref "TP_SWO") (pin "TP") (pinfunction "TP_TP") (pintype "input"))
      (node (ref "U2") (pin "P$AD22") (pinfunction "P1.00_P$AD22") (pintype "bidirectional"))
    )
    (net (code "95") (name "VBAT") (class "Default")
      (node (ref "C37") (pin "2") (pinfunction "2_2") (pintype "passive"))
      (node (ref "C9") (pin "2") (pinfunction "2_2") (pintype "passive"))
      (node (ref "IC2") (pin "C2") (pinfunction "BAT_C2") (pintype "bidirectional"))
      (node (ref "TP_VBAT") (pin "TP") (pinfunction "TP_TP") (pintype "input"))
      (node (ref "U1") (pin "2") (pinfunction "CELL_2") (pintype "power_in"))
      (node (ref "U1") (pin "3") (pinfunction "VDD_3") (pintype "power_in"))
    )
    (net (code "96") (name "VBUS") (class "Default")
      (node (ref "C10") (pin "1") (pinfunction "1_1") (pintype "passive"))
      (node (ref "C32") (pin "1") (pinfunction "1_1") (pintype "passive"))
      (node (ref "C38") (pin "2") (pinfunction "2_2") (pintype "passive"))
      (node (ref "C6") (pin "1") (pinfunction "1_1") (pintype "passive"))
      (node (ref "D4") (pin "5") (pinfunction "VBUS_5") (pintype "bidirectional"))
      (node (ref "IC2") (pin "A2") (pinfunction "IN_A2") (pintype "bidirectional"))
      (node (ref "J1") (pin "A4_B9") (pinfunction "VBUS_A4_B9") (pintype "power_in"))
      (node (ref "J1") (pin "A9_B4") (pinfunction "VBUS_A9_B4") (pintype "power_in"))
      (node (ref "U2") (pin "P$AD2") (pinfunction "VBUS_P$AD2") (pintype "power_in"))
    )
    (net (code "97") (name "VREG") (class "Default")
      (node (ref "C23") (pin "1") (pinfunction "1_1") (pintype "passive"))
      (node (ref "C24") (pin "2") (pinfunction "2_2") (pintype "passive"))
      (node (ref "C39") (pin "1") (pinfunction "1_1") (pintype "passive"))
      (node (ref "IC2") (pin "B2") (pinfunction "SYS_B2") (pintype "bidirectional"))
      (node (ref "IC9") (pin "A1") (pinfunction "EN_A1") (pintype "bidirectional"))
      (node (ref "IC9") (pin "A2") (pinfunction "VIN_1_A2") (pintype "bidirectional"))
      (node (ref "IC9") (pin "A3") (pinfunction "VIN_2_A3") (pintype "bidirectional"))
      (node (ref "TP_VREG") (pin "TP") (pinfunction "TP_TP") (pintype "input"))
    )
    (net (code "98") (name "unconnected-(ANT1-NC-Pad2)") (class "Default")
      (node (ref "ANT1") (pin "2") (pinfunction "NC_2") (pintype "no_connect"))
    )
    (net (code "99") (name "unconnected-(IC3-ASCL-Pad11)") (class "Default")
      (node (ref "IC3") (pin "11") (pinfunction "ASCL_11") (pintype "bidirectional"))
    )
    (net (code "100") (name "unconnected-(IC3-ASDA-Pad4)") (class "Default")
      (node (ref "IC3") (pin "4") (pinfunction "ASDA_4") (pintype "bidirectional"))
    )
    (net (code "101") (name "unconnected-(J1-SBU1-PadA8)") (class "Default")
      (node (ref "J1") (pin "A8") (pinfunction "SBU1_A8") (pintype "bidirectional"))
    )
    (net (code "102") (name "unconnected-(J1-SBU2-PadB8)") (class "Default")
      (node (ref "J1") (pin "B8") (pinfunction "SBU2_B8") (pintype "bidirectional"))
    )
    (net (code "103") (name "unconnected-(J2-Pad1)") (class "Default")
      (node (ref "J2") (pin "1") (pinfunction "1_1") (pintype "bidirectional"))
    )
    (net (code "104") (name "unconnected-(J2-Pad6)") (class "Default")
      (node (ref "J2") (pin "6") (pinfunction "6_6") (pintype "bidirectional"))
    )
    (net (code "105") (name "unconnected-(J2-Pad7)") (class "Default")
      (node (ref "J2") (pin "7") (pinfunction "7_7") (pintype "bidirectional"))
    )
    (net (code "106") (name "unconnected-(U2-DCCH-PadP$AB2)") (class "Default")
      (node (ref "U2") (pin "P$AB2") (pinfunction "DCCH_P$AB2") (pintype "bidirectional"))
    )
  )
)
